# Midi-zu-Usb.net
KiCad netlist of a schematic drawn in EAGLE
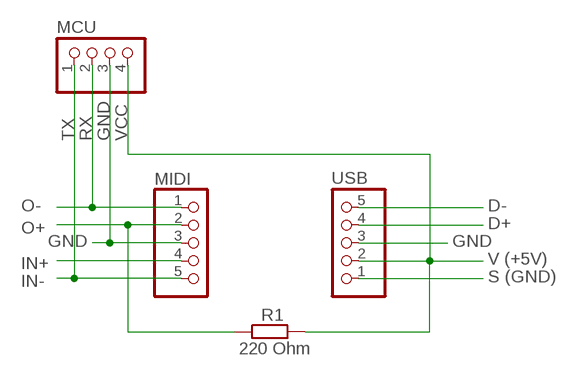
[diagram p0: schematic, sheet 1]

(export (version "E")
  (design (tool "Eeschema 10.0.6"))
  (components
    (comp (ref "MCU")
      (value "PINHD-1X4")
      (footprint "eagle-import:1X04")
      (libsource (lib "eagle-import") (part "PINHD-1X4"))
    )
    (comp (ref "MIDI")
      (value "PINHD-1X5")
      (footprint "eagle-import:1X05")
      (libsource (lib "eagle-import") (part "PINHD-1X5"))
    )
    (comp (ref "R1")
      (value "220 Ohm")
      (footprint "eagle-import:0204_7")
      (libsource (lib "eagle-import") (part "R-EU_0204/7"))
    )
    (comp (ref "USB")
      (value "PINHD-1X5")
      (footprint "eagle-import:1X05")
      (libsource (lib "eagle-import") (part "PINHD-1X5"))
    )
  )
  (nets
    (net (code "1") (name "Net-(MCU-Pad1)") (class "Default")
      (node (ref "MCU") (pin "1") (pinfunction "1_1") (pintype "passive"))
      (node (ref "MIDI") (pin "5") (pinfunction "5_5") (pintype "passive"))
    )
    (net (code "2") (name "Net-(MCU-Pad2)") (class "Default")
      (node (ref "MCU") (pin "2") (pinfunction "2_2") (pintype "passive"))
      (node (ref "MIDI") (pin "1") (pinfunction "1_1") (pintype "passive"))
    )
    (net (code "3") (name "Net-(MCU-Pad3)") (class "Default")
      (node (ref "MCU") (pin "3") (pinfunction "3_3") (pintype "passive"))
      (node (ref "MIDI") (pin "3") (pinfunction "3_3") (pintype "passive"))
    )
    (net (code "4") (name "Net-(MCU-Pad4)") (class "Default")
      (node (ref "MCU") (pin "4") (pinfunction "4_4") (pintype "passive"))
      (node (ref "R1") (pin "2") (pinfunction "2_2") (pintype "passive"))
      (node (ref "USB") (pin "2") (pinfunction "2_2") (pintype "passive"))
    )
    (net (code "5") (name "Net-(MIDI-Pad2)") (class "Default")
      (node (ref "MIDI") (pin "2") (pinfunction "2_2") (pintype "passive"))
      (node (ref "R1") (pin "1") (pinfunction "1_1") (pintype "passive"))
    )
    (net (code "6") (name "unconnected-(MIDI-Pad4)") (class "Default")
      (node (ref "MIDI") (pin "4") (pinfunction "4_4") (pintype "passive"))
    )
    (net (code "7") (name "unconnected-(USB-Pad1)") (class "Default")
      (node (ref "USB") (pin "1") (pinfunction "1_1") (pintype "passive"))
    )
    (net (code "8") (name "unconnected-(USB-Pad3)") (class "Default")
      (node (ref "USB") (pin "3") (pinfunction "3_3") (pintype "passive"))
    )
    (net (code "9") (name "unconnected-(USB-Pad4)") (class "Default")
      (node (ref "USB") (pin "4") (pinfunction "4_4") (pintype "passive"))
    )
    (net (code "10") (name "unconnected-(USB-Pad5)") (class "Default")
      (node (ref "USB") (pin "5") (pinfunction "5_5") (pintype "passive"))
    )
  )
)
